# RK3566_Wi-Fi.net
KiCad netlist of a schematic drawn in Altium Designer
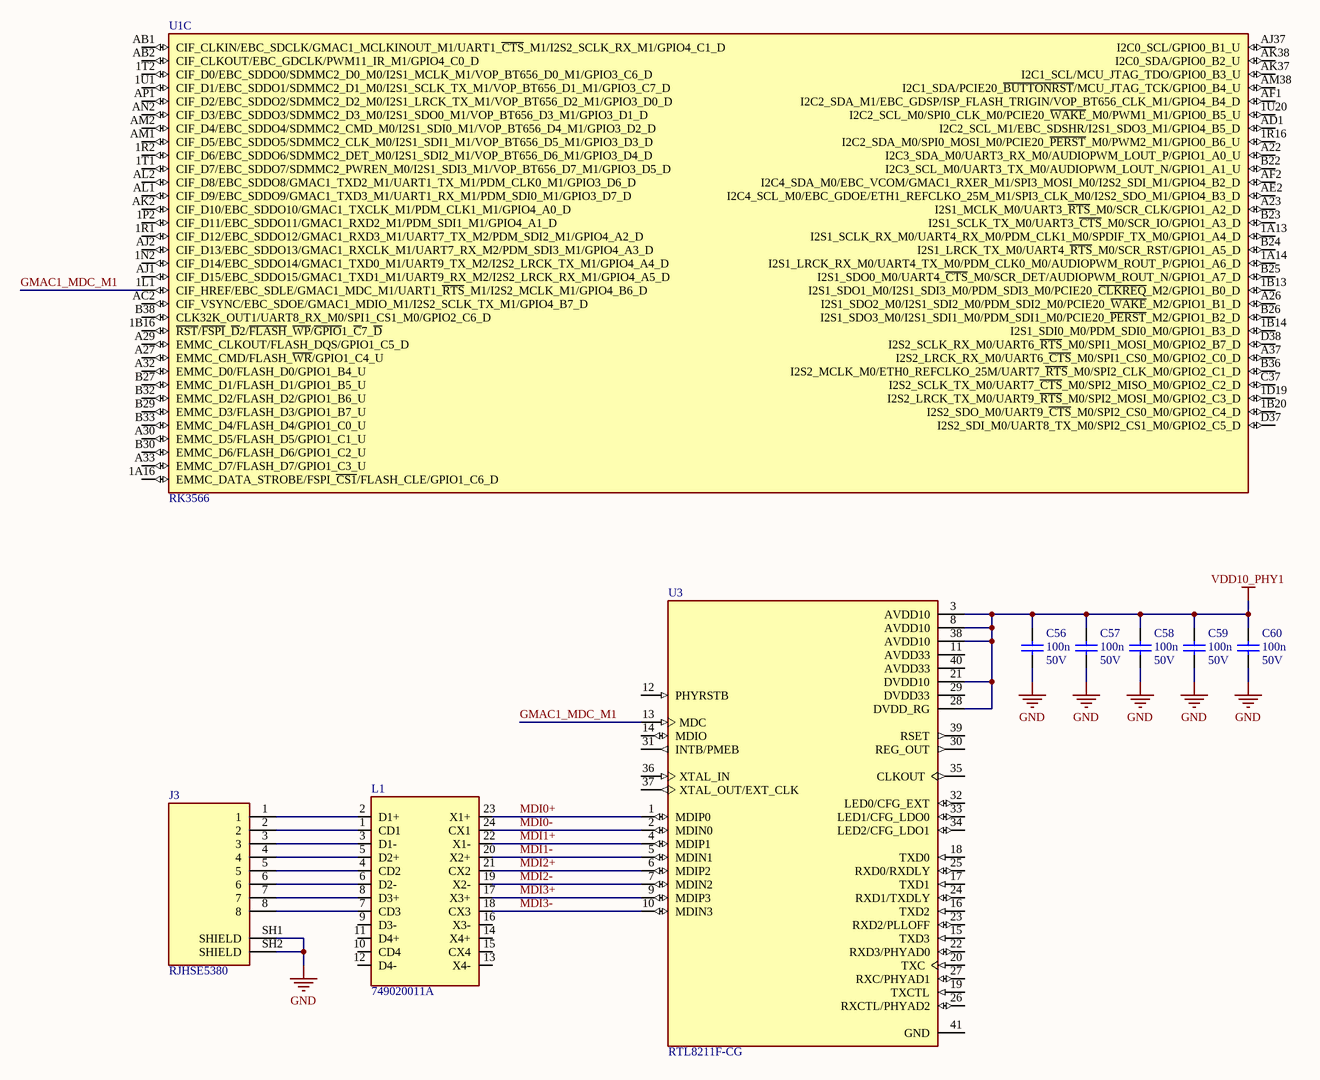
[diagram p0: RK3566_Wi-Fi.SchDoc]

(export (version "E")
  (design (tool "Eeschema 10.0.6"))
  (components
    (comp (ref "C56")
      (value "100n")
      (description "CAP 100N 50V X7R 0402")
      (fields (field (name "VOLTAGE") "50V") (field (name "Comment") "GRM155R71H104KE14D"))
      (libsource (lib "PersonalAltiumLibrary") (part "GRM155R71H104KE14D"))
    )
    (comp (ref "C57")
      (value "100n")
      (description "CAP 100N 50V X7R 0402")
      (fields (field (name "VOLTAGE") "50V") (field (name "Comment") "GRM155R71H104KE14D"))
      (libsource (lib "PersonalAltiumLibrary") (part "GRM155R71H104KE14D"))
    )
    (comp (ref "C58")
      (value "100n")
      (description "CAP 100N 50V X7R 0402")
      (fields (field (name "VOLTAGE") "50V") (field (name "Comment") "GRM155R71H104KE14D"))
      (libsource (lib "PersonalAltiumLibrary") (part "GRM155R71H104KE14D"))
    )
    (comp (ref "C59")
      (value "100n")
      (description "CAP 100N 50V X7R 0402")
      (fields (field (name "VOLTAGE") "50V") (field (name "Comment") "GRM155R71H104KE14D"))
      (libsource (lib "PersonalAltiumLibrary") (part "GRM155R71H104KE14D"))
    )
    (comp (ref "C60")
      (value "100n")
      (description "CAP 100N 50V X7R 0402")
      (fields (field (name "VOLTAGE") "50V") (field (name "Comment") "GRM155R71H104KE14D"))
      (libsource (lib "PersonalAltiumLibrary") (part "GRM155R71H104KE14D"))
    )
    (comp (ref "J3")
      (value "RJHSE5380")
      (footprint "AMPHENOL_RJHSE5380")
      (fields (field (name "MF") "Amphenol"))
      (libsource (lib "PersonalAltiumLibrary") (part "RJHSE5380"))
    )
    (comp (ref "L1")
      (value "749020011A")
      (footprint "WE-LAN_749020011A")
      (description "1000BASE-T LAN transformer, SMD, 24pin, pitch 1.27mm, -40Â°C to +85Â°C, 1.5KVrms isolation, HPLE")
      (fields (field (name "MF") "Wurth Electronics"))
      (libsource (lib "PersonalAltiumLibrary") (part "749020011A"))
    )
    (comp (ref "U1")
      (value "RK3566")
      (footprint "RK3566")
      (description "high-performance and low-power quad-core application processor")
      (fields (field (name "MF") "Fuzhou Rockchip Electronics Co"))
      (libsource (lib "PersonalAltiumLibrary") (part "RK3566"))
    )
    (comp (ref "U3")
      (value "RTL8211F-CG")
      (footprint "QFN40P500X500X90-41N")
      (description "GbE PHY with RGMIII interface & EEE feature (Switch Regulator), QFN40")
      (fields (field (name "MF") "Realtek Semiconductor Corp"))
      (libsource (lib "PersonalAltiumLibrary") (part "RTL8211F-CG"))
    )
  )
  (nets
    (net (code "1") (name "/GMAC1_MDC_M1") (class "Default")
      (node (ref "U1") (pin "1L1") (pinfunction "CIF_HREF/EBC_SDLE/GMAC1_MDC_M1/UART1_~{RTS}_M1/I2S2_MCLK_M1/GPIO4_B6_D_1L1") (pintype "bidirectional"))
      (node (ref "U3") (pin "13") (pinfunction "MDC_13") (pintype "input"))
    )
    (net (code "2") (name "/MDI0+") (class "Default")
      (node (ref "L1") (pin "23") (pinfunction "X1+_23") (pintype "passive"))
      (node (ref "U3") (pin "1") (pinfunction "MDIP0_1") (pintype "bidirectional"))
    )
    (net (code "3") (name "/MDI0-") (class "Default")
      (node (ref "L1") (pin "24") (pinfunction "CX1_24") (pintype "passive"))
      (node (ref "U3") (pin "2") (pinfunction "MDIN0_2") (pintype "bidirectional"))
    )
    (net (code "4") (name "/MDI1+") (class "Default")
      (node (ref "L1") (pin "22") (pinfunction "X1-_22") (pintype "passive"))
      (node (ref "U3") (pin "4") (pinfunction "MDIP1_4") (pintype "bidirectional"))
    )
    (net (code "5") (name "/MDI1-") (class "Default")
      (node (ref "L1") (pin "20") (pinfunction "X2+_20") (pintype "passive"))
      (node (ref "U3") (pin "5") (pinfunction "MDIN1_5") (pintype "bidirectional"))
    )
    (net (code "6") (name "/MDI2+") (class "Default")
      (node (ref "L1") (pin "21") (pinfunction "CX2_21") (pintype "passive"))
      (node (ref "U3") (pin "6") (pinfunction "MDIP2_6") (pintype "bidirectional"))
    )
    (net (code "7") (name "/MDI2-") (class "Default")
      (node (ref "L1") (pin "19") (pinfunction "X2-_19") (pintype "passive"))
      (node (ref "U3") (pin "7") (pinfunction "MDIN2_7") (pintype "bidirectional"))
    )
    (net (code "8") (name "/MDI3+") (class "Default")
      (node (ref "L1") (pin "17") (pinfunction "X3+_17") (pintype "passive"))
      (node (ref "U3") (pin "9") (pinfunction "MDIP3_9") (pintype "bidirectional"))
    )
    (net (code "9") (name "/MDI3-") (class "Default")
      (node (ref "L1") (pin "18") (pinfunction "CX3_18") (pintype "passive"))
      (node (ref "U3") (pin "10") (pinfunction "MDIN3_10") (pintype "bidirectional"))
    )
    (net (code "10") (name "GND") (class "Default")
      (node (ref "C56") (pin "2") (pinfunction "2_2") (pintype "passive"))
      (node (ref "C57") (pin "2") (pinfunction "2_2") (pintype "passive"))
      (node (ref "C58") (pin "2") (pinfunction "2_2") (pintype "passive"))
      (node (ref "C59") (pin "2") (pinfunction "2_2") (pintype "passive"))
      (node (ref "C60") (pin "2") (pinfunction "2_2") (pintype "passive"))
      (node (ref "J3") (pin "SH1") (pinfunction "SHIELD_SH1") (pintype "passive"))
      (node (ref "J3") (pin "SH2") (pinfunction "SHIELD_SH2") (pintype "passive"))
    )
    (net (code "11") (name "Net-(L1-CD1)") (class "Default")
      (node (ref "J3") (pin "2") (pinfunction "2_2") (pintype "passive"))
      (node (ref "L1") (pin "1") (pinfunction "CD1_1") (pintype "passive"))
    )
    (net (code "12") (name "Net-(L1-CD2)") (class "Default")
      (node (ref "J3") (pin "5") (pinfunction "5_5") (pintype "passive"))
      (node (ref "L1") (pin "4") (pinfunction "CD2_4") (pintype "passive"))
    )
    (net (code "13") (name "Net-(L1-CD3)") (class "Default")
      (node (ref "J3") (pin "8") (pinfunction "8_8") (pintype "passive"))
      (node (ref "L1") (pin "7") (pinfunction "CD3_7") (pintype "passive"))
    )
    (net (code "14") (name "Net-(L1-D1+)") (class "Default")
      (node (ref "J3") (pin "1") (pinfunction "1_1") (pintype "passive"))
      (node (ref "L1") (pin "2") (pinfunction "D1+_2") (pintype "passive"))
    )
    (net (code "15") (name "Net-(L1-D1-)") (class "Default")
      (node (ref "J3") (pin "3") (pinfunction "3_3") (pintype "passive"))
      (node (ref "L1") (pin "3") (pinfunction "D1-_3") (pintype "passive"))
    )
    (net (code "16") (name "Net-(L1-D2+)") (class "Default")
      (node (ref "J3") (pin "4") (pinfunction "4_4") (pintype "passive"))
      (node (ref "L1") (pin "5") (pinfunction "D2+_5") (pintype "passive"))
    )
    (net (code "17") (name "Net-(L1-D2-)") (class "Default")
      (node (ref "J3") (pin "6") (pinfunction "6_6") (pintype "passive"))
      (node (ref "L1") (pin "6") (pinfunction "D2-_6") (pintype "passive"))
    )
    (net (code "18") (name "Net-(L1-D3+)") (class "Default")
      (node (ref "J3") (pin "7") (pinfunction "7_7") (pintype "passive"))
      (node (ref "L1") (pin "8") (pinfunction "D3+_8") (pintype "passive"))
    )
    (net (code "19") (name "VDD10_PHY1") (class "Default")
      (node (ref "C56") (pin "1") (pinfunction "1_1") (pintype "passive"))
      (node (ref "C57") (pin "1") (pinfunction "1_1") (pintype "passive"))
      (node (ref "C58") (pin "1") (pinfunction "1_1") (pintype "passive"))
      (node (ref "C59") (pin "1") (pinfunction "1_1") (pintype "passive"))
      (node (ref "C60") (pin "1") (pinfunction "1_1") (pintype "passive"))
      (node (ref "U3") (pin "21") (pinfunction "DVDD10_21") (pintype "power_in"))
      (node (ref "U3") (pin "28") (pinfunction "DVDD_RG_28") (pintype "power_in"))
      (node (ref "U3") (pin "3") (pinfunction "AVDD10_3") (pintype "power_in"))
      (node (ref "U3") (pin "38") (pinfunction "AVDD10_38") (pintype "power_in"))
      (node (ref "U3") (pin "8") (pinfunction "AVDD10_8") (pintype "power_in"))
    )
    (net (code "20") (name "unconnected-(L1-CD4-Pad10)") (class "Default")
      (node (ref "L1") (pin "10") (pinfunction "CD4_10") (pintype "passive"))
    )
    (net (code "21") (name "unconnected-(L1-CX4-Pad15)") (class "Default")
      (node (ref "L1") (pin "15") (pinfunction "CX4_15") (pintype "passive"))
    )
    (net (code "22") (name "unconnected-(L1-D3--Pad9)") (class "Default")
      (node (ref "L1") (pin "9") (pinfunction "D3-_9") (pintype "passive"))
    )
    (net (code "23") (name "unconnected-(L1-D4+-Pad11)") (class "Default")
      (node (ref "L1") (pin "11") (pinfunction "D4+_11") (pintype "passive"))
    )
    (net (code "24") (name "unconnected-(L1-D4--Pad12)") (class "Default")
      (node (ref "L1") (pin "12") (pinfunction "D4-_12") (pintype "passive"))
    )
    (net (code "25") (name "unconnected-(L1-X3--Pad16)") (class "Default")
      (node (ref "L1") (pin "16") (pinfunction "X3-_16") (pintype "passive"))
    )
    (net (code "26") (name "unconnected-(L1-X4+-Pad14)") (class "Default")
      (node (ref "L1") (pin "14") (pinfunction "X4+_14") (pintype "passive"))
    )
    (net (code "27") (name "unconnected-(L1-X4--Pad13)") (class "Default")
      (node (ref "L1") (pin "13") (pinfunction "X4-_13") (pintype "passive"))
    )
    (net (code "28") (name "unconnected-(U1C-CIF_CLKIN{slash}EBC_SDCLK{slash}GMAC1_MCLKINOUT_M1{slash}UART1_~{CTS}_M1{slash}I2S2_SCLK_RX_M1{slash}GPIO4_C1_D-PadAB1)") (class "Default")
      (node (ref "U1") (pin "AB1") (pinfunction "CIF_CLKIN/EBC_SDCLK/GMAC1_MCLKINOUT_M1/UART1_~{CTS}_M1/I2S2_SCLK_RX_M1/GPIO4_C1_D_AB1") (pintype "bidirectional"))
    )
    (net (code "29") (name "unconnected-(U1C-CIF_CLKOUT{slash}EBC_GDCLK{slash}PWM11_IR_M1{slash}GPIO4_C0_D-PadAB2)") (class "Default")
      (node (ref "U1") (pin "AB2") (pinfunction "CIF_CLKOUT/EBC_GDCLK/PWM11_IR_M1/GPIO4_C0_D_AB2") (pintype "bidirectional"))
    )
    (net (code "30") (name "unconnected-(U1C-CIF_D0{slash}EBC_SDDO0{slash}SDMMC2_D0_M0{slash}I2S1_MCLK_M1{slash}VOP_BT656_D0_M1{slash}GPIO3_C6_D-Pad1T2)") (class "Default")
      (node (ref "U1") (pin "1T2") (pinfunction "CIF_D0/EBC_SDDO0/SDMMC2_D0_M0/I2S1_MCLK_M1/VOP_BT656_D0_M1/GPIO3_C6_D_1T2") (pintype "bidirectional"))
    )
    (net (code "31") (name "unconnected-(U1C-CIF_D1{slash}EBC_SDDO1{slash}SDMMC2_D1_M0{slash}I2S1_SCLK_TX_M1{slash}VOP_BT656_D1_M1{slash}GPIO3_C7_D-Pad1U1)") (class "Default")
      (node (ref "U1") (pin "1U1") (pinfunction "CIF_D1/EBC_SDDO1/SDMMC2_D1_M0/I2S1_SCLK_TX_M1/VOP_BT656_D1_M1/GPIO3_C7_D_1U1") (pintype "bidirectional"))
    )
    (net (code "32") (name "unconnected-(U1C-CIF_D2{slash}EBC_SDDO2{slash}SDMMC2_D2_M0{slash}I2S1_LRCK_TX_M1{slash}VOP_BT656_D2_M1{slash}GPIO3_D0_D-PadAP1)") (class "Default")
      (node (ref "U1") (pin "AP1") (pinfunction "CIF_D2/EBC_SDDO2/SDMMC2_D2_M0/I2S1_LRCK_TX_M1/VOP_BT656_D2_M1/GPIO3_D0_D_AP1") (pintype "bidirectional"))
    )
    (net (code "33") (name "unconnected-(U1C-CIF_D3{slash}EBC_SDDO3{slash}SDMMC2_D3_M0{slash}I2S1_SDO0_M1{slash}VOP_BT656_D3_M1{slash}GPIO3_D1_D-PadAN2)") (class "Default")
      (node (ref "U1") (pin "AN2") (pinfunction "CIF_D3/EBC_SDDO3/SDMMC2_D3_M0/I2S1_SDO0_M1/VOP_BT656_D3_M1/GPIO3_D1_D_AN2") (pintype "bidirectional"))
    )
    (net (code "34") (name "unconnected-(U1C-CIF_D4{slash}EBC_SDDO4{slash}SDMMC2_CMD_M0{slash}I2S1_SDI0_M1{slash}VOP_BT656_D4_M1{slash}GPIO3_D2_D-PadAM2)") (class "Default")
      (node (ref "U1") (pin "AM2") (pinfunction "CIF_D4/EBC_SDDO4/SDMMC2_CMD_M0/I2S1_SDI0_M1/VOP_BT656_D4_M1/GPIO3_D2_D_AM2") (pintype "bidirectional"))
    )
    (net (code "35") (name "unconnected-(U1C-CIF_D5{slash}EBC_SDDO5{slash}SDMMC2_CLK_M0{slash}I2S1_SDI1_M1{slash}VOP_BT656_D5_M1{slash}GPIO3_D3_D-PadAM1)") (class "Default")
      (node (ref "U1") (pin "AM1") (pinfunction "CIF_D5/EBC_SDDO5/SDMMC2_CLK_M0/I2S1_SDI1_M1/VOP_BT656_D5_M1/GPIO3_D3_D_AM1") (pintype "bidirectional"))
    )
    (net (code "36") (name "unconnected-(U1C-CIF_D6{slash}EBC_SDDO6{slash}SDMMC2_DET_M0{slash}I2S1_SDI2_M1{slash}VOP_BT656_D6_M1{slash}GPIO3_D4_D-Pad1R2)") (class "Default")
      (node (ref "U1") (pin "1R2") (pinfunction "CIF_D6/EBC_SDDO6/SDMMC2_DET_M0/I2S1_SDI2_M1/VOP_BT656_D6_M1/GPIO3_D4_D_1R2") (pintype "bidirectional"))
    )
    (net (code "37") (name "unconnected-(U1C-CIF_D7{slash}EBC_SDDO7{slash}SDMMC2_PWREN_M0{slash}I2S1_SDI3_M1{slash}VOP_BT656_D7_M1{slash}GPIO3_D5_D-Pad1T1)") (class "Default")
      (node (ref "U1") (pin "1T1") (pinfunction "CIF_D7/EBC_SDDO7/SDMMC2_PWREN_M0/I2S1_SDI3_M1/VOP_BT656_D7_M1/GPIO3_D5_D_1T1") (pintype "bidirectional"))
    )
    (net (code "38") (name "unconnected-(U1C-CIF_D8{slash}EBC_SDDO8{slash}GMAC1_TXD2_M1{slash}UART1_TX_M1{slash}PDM_CLK0_M1{slash}GPIO3_D6_D-PadAL2)") (class "Default")
      (node (ref "U1") (pin "AL2") (pinfunction "CIF_D8/EBC_SDDO8/GMAC1_TXD2_M1/UART1_TX_M1/PDM_CLK0_M1/GPIO3_D6_D_AL2") (pintype "bidirectional"))
    )
    (net (code "39") (name "unconnected-(U1C-CIF_D9{slash}EBC_SDDO9{slash}GMAC1_TXD3_M1{slash}UART1_RX_M1{slash}PDM_SDI0_M1{slash}GPIO3_D7_D-PadAL1)") (class "Default")
      (node (ref "U1") (pin "AL1") (pinfunction "CIF_D9/EBC_SDDO9/GMAC1_TXD3_M1/UART1_RX_M1/PDM_SDI0_M1/GPIO3_D7_D_AL1") (pintype "bidirectional"))
    )
    (net (code "40") (name "unconnected-(U1C-CIF_D10{slash}EBC_SDDO10{slash}GMAC1_TXCLK_M1{slash}PDM_CLK1_M1{slash}GPIO4_A0_D-PadAK2)") (class "Default")
      (node (ref "U1") (pin "AK2") (pinfunction "CIF_D10/EBC_SDDO10/GMAC1_TXCLK_M1/PDM_CLK1_M1/GPIO4_A0_D_AK2") (pintype "bidirectional"))
    )
    (net (code "41") (name "unconnected-(U1C-CIF_D11{slash}EBC_SDDO11{slash}GMAC1_RXD2_M1{slash}PDM_SDI1_M1{slash}GPIO4_A1_D-Pad1P2)") (class "Default")
      (node (ref "U1") (pin "1P2") (pinfunction "CIF_D11/EBC_SDDO11/GMAC1_RXD2_M1/PDM_SDI1_M1/GPIO4_A1_D_1P2") (pintype "bidirectional"))
    )
    (net (code "42") (name "unconnected-(U1C-CIF_D12{slash}EBC_SDDO12{slash}GMAC1_RXD3_M1{slash}UART7_TX_M2{slash}PDM_SDI2_M1{slash}GPIO4_A2_D-Pad1R1)") (class "Default")
      (node (ref "U1") (pin "1R1") (pinfunction "CIF_D12/EBC_SDDO12/GMAC1_RXD3_M1/UART7_TX_M2/PDM_SDI2_M1/GPIO4_A2_D_1R1") (pintype "bidirectional"))
    )
    (net (code "43") (name "unconnected-(U1C-CIF_D13{slash}EBC_SDDO13{slash}GMAC1_RXCLK_M1{slash}UART7_RX_M2{slash}PDM_SDI3_M1{slash}GPIO4_A3_D-PadAJ2)") (class "Default")
      (node (ref "U1") (pin "AJ2") (pinfunction "CIF_D13/EBC_SDDO13/GMAC1_RXCLK_M1/UART7_RX_M2/PDM_SDI3_M1/GPIO4_A3_D_AJ2") (pintype "bidirectional"))
    )
    (net (code "44") (name "unconnected-(U1C-CIF_D14{slash}EBC_SDDO14{slash}GMAC1_TXD0_M1{slash}UART9_TX_M2{slash}I2S2_LRCK_TX_M1{slash}GPIO4_A4_D-Pad1N2)") (class "Default")
      (node (ref "U1") (pin "1N2") (pinfunction "CIF_D14/EBC_SDDO14/GMAC1_TXD0_M1/UART9_TX_M2/I2S2_LRCK_TX_M1/GPIO4_A4_D_1N2") (pintype "bidirectional"))
    )
    (net (code "45") (name "unconnected-(U1C-CIF_D15{slash}EBC_SDDO15{slash}GMAC1_TXD1_M1{slash}UART9_RX_M2{slash}I2S2_LRCK_RX_M1{slash}GPIO4_A5_D-PadAJ1)") (class "Default")
      (node (ref "U1") (pin "AJ1") (pinfunction "CIF_D15/EBC_SDDO15/GMAC1_TXD1_M1/UART9_RX_M2/I2S2_LRCK_RX_M1/GPIO4_A5_D_AJ1") (pintype "bidirectional"))
    )
    (net (code "46") (name "unconnected-(U1C-CIF_VSYNC{slash}EBC_SDOE{slash}GMAC1_MDIO_M1{slash}I2S2_SCLK_TX_M1{slash}GPIO4_B7_D-PadAC2)") (class "Default")
      (node (ref "U1") (pin "AC2") (pinfunction "CIF_VSYNC/EBC_SDOE/GMAC1_MDIO_M1/I2S2_SCLK_TX_M1/GPIO4_B7_D_AC2") (pintype "bidirectional"))
    )
    (net (code "47") (name "unconnected-(U1C-CLK32K_OUT1{slash}UART8_RX_M0{slash}SPI1_CS1_M0{slash}GPIO2_C6_D-PadB38)") (class "Default")
      (node (ref "U1") (pin "B38") (pinfunction "CLK32K_OUT1/UART8_RX_M0/SPI1_CS1_M0/GPIO2_C6_D_B38") (pintype "bidirectional"))
    )
    (net (code "48") (name "unconnected-(U1C-EMMC_CLKOUT{slash}FLASH_DQS{slash}GPIO1_C5_D-PadA29)") (class "Default")
      (node (ref "U1") (pin "A29") (pinfunction "EMMC_CLKOUT/FLASH_DQS/GPIO1_C5_D_A29") (pintype "bidirectional"))
    )
    (net (code "49") (name "unconnected-(U1C-EMMC_CMD{slash}FLASH_~{WR}{slash}GPIO1_C4_U-PadA27)") (class "Default")
      (node (ref "U1") (pin "A27") (pinfunction "EMMC_CMD/FLASH_~{WR}/GPIO1_C4_U_A27") (pintype "bidirectional"))
    )
    (net (code "50") (name "unconnected-(U1C-EMMC_D0{slash}FLASH_D0{slash}GPIO1_B4_U-PadA32)") (class "Default")
      (node (ref "U1") (pin "A32") (pinfunction "EMMC_D0/FLASH_D0/GPIO1_B4_U_A32") (pintype "bidirectional"))
    )
    (net (code "51") (name "unconnected-(U1C-EMMC_D1{slash}FLASH_D1{slash}GPIO1_B5_U-PadB27)") (class "Default")
      (node (ref "U1") (pin "B27") (pinfunction "EMMC_D1/FLASH_D1/GPIO1_B5_U_B27") (pintype "bidirectional"))
    )
    (net (code "52") (name "unconnected-(U1C-EMMC_D2{slash}FLASH_D2{slash}GPIO1_B6_U-PadB32)") (class "Default")
      (node (ref "U1") (pin "B32") (pinfunction "EMMC_D2/FLASH_D2/GPIO1_B6_U_B32") (pintype "bidirectional"))
    )
    (net (code "53") (name "unconnected-(U1C-EMMC_D3{slash}FLASH_D3{slash}GPIO1_B7_U-PadB29)") (class "Default")
      (node (ref "U1") (pin "B29") (pinfunction "EMMC_D3/FLASH_D3/GPIO1_B7_U_B29") (pintype "bidirectional"))
    )
    (net (code "54") (name "unconnected-(U1C-EMMC_D4{slash}FLASH_D4{slash}GPIO1_C0_U-PadB33)") (class "Default")
      (node (ref "U1") (pin "B33") (pinfunction "EMMC_D4/FLASH_D4/GPIO1_C0_U_B33") (pintype "bidirectional"))
    )
    (net (code "55") (name "unconnected-(U1C-EMMC_D5{slash}FLASH_D5{slash}GPIO1_C1_U-PadA30)") (class "Default")
      (node (ref "U1") (pin "A30") (pinfunction "EMMC_D5/FLASH_D5/GPIO1_C1_U_A30") (pintype "bidirectional"))
    )
    (net (code "56") (name "unconnected-(U1C-EMMC_D6{slash}FLASH_D6{slash}GPIO1_C2_U-PadB30)") (class "Default")
      (node (ref "U1") (pin "B30") (pinfunction "EMMC_D6/FLASH_D6/GPIO1_C2_U_B30") (pintype "bidirectional"))
    )
    (net (code "57") (name "unconnected-(U1C-EMMC_D7{slash}FLASH_D7{slash}GPIO1_C3_U-PadA33)") (class "Default")
      (node (ref "U1") (pin "A33") (pinfunction "EMMC_D7/FLASH_D7/GPIO1_C3_U_A33") (pintype "bidirectional"))
    )
    (net (code "58") (name "unconnected-(U1C-EMMC_DATA_STROBE{slash}FSPI_~{CS1}{slash}FLASH_CLE{slash}GPIO1_C6_D-Pad1A16)") (class "Default")
      (node (ref "U1") (pin "1A16") (pinfunction "EMMC_DATA_STROBE/FSPI_~{CS1}/FLASH_CLE/GPIO1_C6_D_1A16") (pintype "bidirectional"))
    )
    (net (code "59") (name "unconnected-(U1C-I2C0_SCL{slash}GPIO0_B1_U-PadAJ37)") (class "Default")
      (node (ref "U1") (pin "AJ37") (pinfunction "I2C0_SCL/GPIO0_B1_U_AJ37") (pintype "bidirectional"))
    )
    (net (code "60") (name "unconnected-(U1C-I2C0_SDA{slash}GPIO0_B2_U-PadAK38)") (class "Default")
      (node (ref "U1") (pin "AK38") (pinfunction "I2C0_SDA/GPIO0_B2_U_AK38") (pintype "bidirectional"))
    )
    (net (code "61") (name "unconnected-(U1C-I2C1_SCL{slash}MCU_JTAG_TDO{slash}GPIO0_B3_U-PadAK37)") (class "Default")
      (node (ref "U1") (pin "AK37") (pinfunction "I2C1_SCL/MCU_JTAG_TDO/GPIO0_B3_U_AK37") (pintype "bidirectional"))
    )
    (net (code "62") (name "unconnected-(U1C-I2C1_SDA{slash}PCIE20_~{BUTTONRST}{slash}MCU_JTAG_TCK{slash}GPIO0_B4_U-PadAM38)") (class "Default")
      (node (ref "U1") (pin "AM38") (pinfunction "I2C1_SDA/PCIE20_~{BUTTONRST}/MCU_JTAG_TCK/GPIO0_B4_U_AM38") (pintype "bidirectional"))
    )
    (net (code "63") (name "unconnected-(U1C-I2C2_SCL_M0{slash}SPI0_CLK_M0{slash}PCIE20_~{WAKE}_M0{slash}PWM1_M1{slash}GPIO0_B5_U-Pad1U20)") (class "Default")
      (node (ref "U1") (pin "1U20") (pinfunction "I2C2_SCL_M0/SPI0_CLK_M0/PCIE20_~{WAKE}_M0/PWM1_M1/GPIO0_B5_U_1U20") (pintype "bidirectional"))
    )
    (net (code "64") (name "unconnected-(U1C-I2C2_SCL_M1{slash}EBC_SDSHR{slash}I2S1_SDO3_M1{slash}GPIO4_B5_D-PadAD1)") (class "Default")
      (node (ref "U1") (pin "AD1") (pinfunction "I2C2_SCL_M1/EBC_SDSHR/I2S1_SDO3_M1/GPIO4_B5_D_AD1") (pintype "bidirectional"))
    )
    (net (code "65") (name "unconnected-(U1C-I2C2_SDA_M0{slash}SPI0_MOSI_M0{slash}PCIE20_~{PERST}_M0{slash}PWM2_M1{slash}GPIO0_B6_U-Pad1R16)") (class "Default")
      (node (ref "U1") (pin "1R16") (pinfunction "I2C2_SDA_M0/SPI0_MOSI_M0/PCIE20_~{PERST}_M0/PWM2_M1/GPIO0_B6_U_1R16") (pintype "bidirectional"))
    )
    (net (code "66") (name "unconnected-(U1C-I2C2_SDA_M1{slash}EBC_GDSP{slash}ISP_FLASH_TRIGIN{slash}VOP_BT656_CLK_M1{slash}GPIO4_B4_D-PadAF1)") (class "Default")
      (node (ref "U1") (pin "AF1") (pinfunction "I2C2_SDA_M1/EBC_GDSP/ISP_FLASH_TRIGIN/VOP_BT656_CLK_M1/GPIO4_B4_D_AF1") (pintype "bidirectional"))
    )
    (net (code "67") (name "unconnected-(U1C-I2C3_SCL_M0{slash}UART3_TX_M0{slash}AUDIOPWM_LOUT_N{slash}GPIO1_A1_U-PadB22)") (class "Default")
      (node (ref "U1") (pin "B22") (pinfunction "I2C3_SCL_M0/UART3_TX_M0/AUDIOPWM_LOUT_N/GPIO1_A1_U_B22") (pintype "bidirectional"))
    )
    (net (code "68") (name "unconnected-(U1C-I2C3_SDA_M0{slash}UART3_RX_M0{slash}AUDIOPWM_LOUT_P{slash}GPIO1_A0_U-PadA22)") (class "Default")
      (node (ref "U1") (pin "A22") (pinfunction "I2C3_SDA_M0/UART3_RX_M0/AUDIOPWM_LOUT_P/GPIO1_A0_U_A22") (pintype "bidirectional"))
    )
    (net (code "69") (name "unconnected-(U1C-I2C4_SCL_M0{slash}EBC_GDOE{slash}ETH1_REFCLKO_25M_M1{slash}SPI3_CLK_M0{slash}I2S2_SDO_M1{slash}GPIO4_B3_D-PadAE2)") (class "Default")
      (node (ref "U1") (pin "AE2") (pinfunction "I2C4_SCL_M0/EBC_GDOE/ETH1_REFCLKO_25M_M1/SPI3_CLK_M0/I2S2_SDO_M1/GPIO4_B3_D_AE2") (pintype "bidirectional"))
    )
    (net (code "70") (name "unconnected-(U1C-I2C4_SDA_M0{slash}EBC_VCOM{slash}GMAC1_RXER_M1{slash}SPI3_MOSI_M0{slash}I2S2_SDI_M1{slash}GPIO4_B2_D-PadAF2)") (class "Default")
      (node (ref "U1") (pin "AF2") (pinfunction "I2C4_SDA_M0/EBC_VCOM/GMAC1_RXER_M1/SPI3_MOSI_M0/I2S2_SDI_M1/GPIO4_B2_D_AF2") (pintype "bidirectional"))
    )
    (net (code "71") (name "unconnected-(U1C-I2S1_LRCK_RX_M0{slash}UART4_TX_M0{slash}PDM_CLK0_M0{slash}AUDIOPWM_ROUT_P{slash}GPIO1_A6_D-Pad1A14)") (class "Default")
      (node (ref "U1") (pin "1A14") (pinfunction "I2S1_LRCK_RX_M0/UART4_TX_M0/PDM_CLK0_M0/AUDIOPWM_ROUT_P/GPIO1_A6_D_1A14") (pintype "bidirectional"))
    )
    (net (code "72") (name "unconnected-(U1C-I2S1_LRCK_TX_M0{slash}UART4_~{RTS}_M0{slash}SCR_RST{slash}GPIO1_A5_D-PadB24)") (class "Default")
      (node (ref "U1") (pin "B24") (pinfunction "I2S1_LRCK_TX_M0/UART4_~{RTS}_M0/SCR_RST/GPIO1_A5_D_B24") (pintype "bidirectional"))
    )
    (net (code "73") (name "unconnected-(U1C-I2S1_MCLK_M0{slash}UART3_~{RTS}_M0{slash}SCR_CLK{slash}GPIO1_A2_D-PadA23)") (class "Default")
      (node (ref "U1") (pin "A23") (pinfunction "I2S1_MCLK_M0/UART3_~{RTS}_M0/SCR_CLK/GPIO1_A2_D_A23") (pintype "bidirectional"))
    )
    (net (code "74") (name "unconnected-(U1C-I2S1_SCLK_RX_M0{slash}UART4_RX_M0{slash}PDM_CLK1_M0{slash}SPDIF_TX_M0{slash}GPIO1_A4_D-Pad1A13)") (class "Default")
      (node (ref "U1") (pin "1A13") (pinfunction "I2S1_SCLK_RX_M0/UART4_RX_M0/PDM_CLK1_M0/SPDIF_TX_M0/GPIO1_A4_D_1A13") (pintype "bidirectional"))
    )
    (net (code "75") (name "unconnected-(U1C-I2S1_SCLK_TX_M0{slash}UART3_~{CTS}_M0{slash}SCR_IO{slash}GPIO1_A3_D-PadB23)") (class "Default")
      (node (ref "U1") (pin "B23") (pinfunction "I2S1_SCLK_TX_M0/UART3_~{CTS}_M0/SCR_IO/GPIO1_A3_D_B23") (pintype "bidirectional"))
    )
    (net (code "76") (name "unconnected-(U1C-I2S1_SDI0_M0{slash}PDM_SDI0_M0{slash}GPIO1_B3_D-Pad1B14)") (class "Default")
      (node (ref "U1") (pin "1B14") (pinfunction "I2S1_SDI0_M0/PDM_SDI0_M0/GPIO1_B3_D_1B14") (pintype "bidirectional"))
    )
    (net (code "77") (name "unconnected-(U1C-I2S1_SDO0_M0{slash}UART4_~{CTS}_M0{slash}SCR_DET{slash}AUDIOPWM_ROUT_N{slash}GPIO1_A7_D-PadB25)") (class "Default")
      (node (ref "U1") (pin "B25") (pinfunction "I2S1_SDO0_M0/UART4_~{CTS}_M0/SCR_DET/AUDIOPWM_ROUT_N/GPIO1_A7_D_B25") (pintype "bidirectional"))
    )
    (net (code "78") (name "unconnected-(U1C-I2S1_SDO1_M0{slash}I2S1_SDI3_M0{slash}PDM_SDI3_M0{slash}PCIE20_~{CLKREQ}_M2{slash}GPIO1_B0_D-Pad1B13)") (class "Default")
      (node (ref "U1") (pin "1B13") (pinfunction "I2S1_SDO1_M0/I2S1_SDI3_M0/PDM_SDI3_M0/PCIE20_~{CLKREQ}_M2/GPIO1_B0_D_1B13") (pintype "bidirectional"))
    )
    (net (code "79") (name "unconnected-(U1C-I2S1_SDO2_M0{slash}I2S1_SDI2_M0{slash}PDM_SDI2_M0{slash}PCIE20_~{WAKE}_M2{slash}GPIO1_B1_D-PadA26)") (class "Default")
      (node (ref "U1") (pin "A26") (pinfunction "I2S1_SDO2_M0/I2S1_SDI2_M0/PDM_SDI2_M0/PCIE20_~{WAKE}_M2/GPIO1_B1_D_A26") (pintype "bidirectional"))
    )
    (net (code "80") (name "unconnected-(U1C-I2S1_SDO3_M0{slash}I2S1_SDI1_M0{slash}PDM_SDI1_M0{slash}PCIE20_~{PERST}_M2{slash}GPIO1_B2_D-PadB26)") (class "Default")
      (node (ref "U1") (pin "B26") (pinfunction "I2S1_SDO3_M0/I2S1_SDI1_M0/PDM_SDI1_M0/PCIE20_~{PERST}_M2/GPIO1_B2_D_B26") (pintype "bidirectional"))
    )
    (net (code "81") (name "unconnected-(U1C-I2S2_LRCK_RX_M0{slash}UART6_~{CTS}_M0{slash}SPI1_CS0_M0{slash}GPIO2_C0_D-PadA37)") (class "Default")
      (node (ref "U1") (pin "A37") (pinfunction "I2S2_LRCK_RX_M0/UART6_~{CTS}_M0/SPI1_CS0_M0/GPIO2_C0_D_A37") (pintype "bidirectional"))
    )
    (net (code "82") (name "unconnected-(U1C-I2S2_LRCK_TX_M0{slash}UART9_~{RTS}_M0{slash}SPI2_MOSI_M0{slash}GPIO2_C3_D-Pad1D19)") (class "Default")
      (node (ref "U1") (pin "1D19") (pinfunction "I2S2_LRCK_TX_M0/UART9_~{RTS}_M0/SPI2_MOSI_M0/GPIO2_C3_D_1D19") (pintype "bidirectional"))
    )
    (net (code "83") (name "unconnected-(U1C-I2S2_MCLK_M0{slash}ETH0_REFCLKO_25M{slash}UART7_~{RTS}_M0{slash}SPI2_CLK_M0{slash}GPIO2_C1_D-PadB36)") (class "Default")
      (node (ref "U1") (pin "B36") (pinfunction "I2S2_MCLK_M0/ETH0_REFCLKO_25M/UART7_~{RTS}_M0/SPI2_CLK_M0/GPIO2_C1_D_B36") (pintype "bidirectional"))
    )
    (net (code "84") (name "unconnected-(U1C-I2S2_SCLK_RX_M0{slash}UART6_~{RTS}_M0{slash}SPI1_MOSI_M0{slash}GPIO2_B7_D-PadD38)") (class "Default")
      (node (ref "U1") (pin "D38") (pinfunction "I2S2_SCLK_RX_M0/UART6_~{RTS}_M0/SPI1_MOSI_M0/GPIO2_B7_D_D38") (pintype "bidirectional"))
    )
    (net (code "85") (name "unconnected-(U1C-I2S2_SCLK_TX_M0{slash}UART7_~{CTS}_M0{slash}SPI2_MISO_M0{slash}GPIO2_C2_D-PadC37)") (class "Default")
      (node (ref "U1") (pin "C37") (pinfunction "I2S2_SCLK_TX_M0/UART7_~{CTS}_M0/SPI2_MISO_M0/GPIO2_C2_D_C37") (pintype "bidirectional"))
    )
    (net (code "86") (name "unconnected-(U1C-I2S2_SDI_M0{slash}UART8_TX_M0{slash}SPI2_CS1_M0{slash}GPIO2_C5_D-PadD37)") (class "Default")
      (node (ref "U1") (pin "D37") (pinfunction "I2S2_SDI_M0/UART8_TX_M0/SPI2_CS1_M0/GPIO2_C5_D_D37") (pintype "bidirectional"))
    )
    (net (code "87") (name "unconnected-(U1C-I2S2_SDO_M0{slash}UART9_~{CTS}_M0{slash}SPI2_CS0_M0{slash}GPIO2_C4_D-Pad1B20)") (class "Default")
      (node (ref "U1") (pin "1B20") (pinfunction "I2S2_SDO_M0/UART9_~{CTS}_M0/SPI2_CS0_M0/GPIO2_C4_D_1B20") (pintype "bidirectional"))
    )
    (net (code "88") (name "unconnected-(U1C-~{RST}{slash}~{FSPI}_~{D}2{slash}~{FLASH}_~{WP}{slash}~{GPIO}1_~{C}7_~{D}-Pad1B16)") (class "Default")
      (node (ref "U1") (pin "1B16") (pinfunction "~{RST}/~{FSPI}_~{D}2/~{FLASH}_~{WP}/~{GPIO}1_~{C}7_~{D}_1B16") (pintype "bidirectional"))
    )
    (net (code "89") (name "unconnected-(U3-AVDD33-Pad11)") (class "Default")
      (node (ref "U3") (pin "11") (pinfunction "AVDD33_11") (pintype "power_in"))
    )
    (net (code "90") (name "unconnected-(U3-AVDD33-Pad40)") (class "Default")
      (node (ref "U3") (pin "40") (pinfunction "AVDD33_40") (pintype "power_in"))
    )
    (net (code "91") (name "unconnected-(U3-CLKOUT-Pad35)") (class "Default")
      (node (ref "U3") (pin "35") (pinfunction "CLKOUT_35") (pintype "output"))
    )
    (net (code "92") (name "unconnected-(U3-DVDD33-Pad29)") (class "Default")
      (node (ref "U3") (pin "29") (pinfunction "DVDD33_29") (pintype "power_in"))
    )
    (net (code "93") (name "unconnected-(U3-GND-Pad41)") (class "Default")
      (node (ref "U3") (pin "41") (pinfunction "GND_41") (pintype "power_in"))
    )
    (net (code "94") (name "unconnected-(U3-INTB{slash}PMEB-Pad31)") (class "Default")
      (node (ref "U3") (pin "31") (pinfunction "INTB/PMEB_31") (pintype "output"))
    )
    (net (code "95") (name "unconnected-(U3-LED0{slash}CFG_EXT-Pad32)") (class "Default")
      (node (ref "U3") (pin "32") (pinfunction "LED0/CFG_EXT_32") (pintype "bidirectional"))
    )
    (net (code "96") (name "unconnected-(U3-LED1{slash}CFG_LDO0-Pad33)") (class "Default")
      (node (ref "U3") (pin "33") (pinfunction "LED1/CFG_LDO0_33") (pintype "bidirectional"))
    )
    (net (code "97") (name "unconnected-(U3-LED2{slash}CFG_LDO1-Pad34)") (class "Default")
      (node (ref "U3") (pin "34") (pinfunction "LED2/CFG_LDO1_34") (pintype "bidirectional"))
    )
    (net (code "98") (name "unconnected-(U3-MDIO-Pad14)") (class "Default")
      (node (ref "U3") (pin "14") (pinfunction "MDIO_14") (pintype "bidirectional"))
    )
    (net (code "99") (name "unconnected-(U3-PHYRSTB-Pad12)") (class "Default")
      (node (ref "U3") (pin "12") (pinfunction "PHYRSTB_12") (pintype "input"))
    )
    (net (code "100") (name "unconnected-(U3-REG_OUT-Pad30)") (class "Default")
      (node (ref "U3") (pin "30") (pinfunction "REG_OUT_30") (pintype "output"))
    )
    (net (code "101") (name "unconnected-(U3-RSET-Pad39)") (class "Default")
      (node (ref "U3") (pin "39") (pinfunction "RSET_39") (pintype "output"))
    )
    (net (code "102") (name "unconnected-(U3-RXCTL{slash}PHYAD2-Pad26)") (class "Default")
      (node (ref "U3") (pin "26") (pinfunction "RXCTL/PHYAD2_26") (pintype "bidirectional"))
    )
    (net (code "103") (name "unconnected-(U3-RXC{slash}PHYAD1-Pad27)") (class "Default")
      (node (ref "U3") (pin "27") (pinfunction "RXC/PHYAD1_27") (pintype "bidirectional"))
    )
    (net (code "104") (name "unconnected-(U3-RXD0{slash}RXDLY-Pad25)") (class "Default")
      (node (ref "U3") (pin "25") (pinfunction "RXD0/RXDLY_25") (pintype "bidirectional"))
    )
    (net (code "105") (name "unconnected-(U3-RXD1{slash}TXDLY-Pad24)") (class "Default")
      (node (ref "U3") (pin "24") (pinfunction "RXD1/TXDLY_24") (pintype "bidirectional"))
    )
    (net (code "106") (name "unconnected-(U3-RXD2{slash}PLLOFF-Pad23)") (class "Default")
      (node (ref "U3") (pin "23") (pinfunction "RXD2/PLLOFF_23") (pintype "bidirectional"))
    )
    (net (code "107") (name "unconnected-(U3-RXD3{slash}PHYAD0-Pad22)") (class "Default")
      (node (ref "U3") (pin "22") (pinfunction "RXD3/PHYAD0_22") (pintype "bidirectional"))
    )
    (net (code "108") (name "unconnected-(U3-TXC-Pad20)") (class "Default")
      (node (ref "U3") (pin "20") (pinfunction "TXC_20") (pintype "input"))
    )
    (net (code "109") (name "unconnected-(U3-TXCTL-Pad19)") (class "Default")
      (node (ref "U3") (pin "19") (pinfunction "TXCTL_19") (pintype "input"))
    )
    (net (code "110") (name "unconnected-(U3-TXD0-Pad18)") (class "Default")
      (node (ref "U3") (pin "18") (pinfunction "TXD0_18") (pintype "input"))
    )
    (net (code "111") (name "unconnected-(U3-TXD1-Pad17)") (class "Default")
      (node (ref "U3") (pin "17") (pinfunction "TXD1_17") (pintype "input"))
    )
    (net (code "112") (name "unconnected-(U3-TXD2-Pad16)") (class "Default")
      (node (ref "U3") (pin "16") (pinfunction "TXD2_16") (pintype "input"))
    )
    (net (code "113") (name "unconnected-(U3-TXD3-Pad15)") (class "Default")
      (node (ref "U3") (pin "15") (pinfunction "TXD3_15") (pintype "input"))
    )
    (net (code "114") (name "unconnected-(U3-XTAL_IN-Pad36)") (class "Default")
      (node (ref "U3") (pin "36") (pinfunction "XTAL_IN_36") (pintype "input"))
    )
    (net (code "115") (name "unconnected-(U3-XTAL_OUT{slash}EXT_CLK-Pad37)") (class "Default")
      (node (ref "U3") (pin "37") (pinfunction "XTAL_OUT/EXT_CLK_37") (pintype "output"))
    )
  )
)
